# Port.net
KiCad netlist of a schematic drawn in Altium Designer
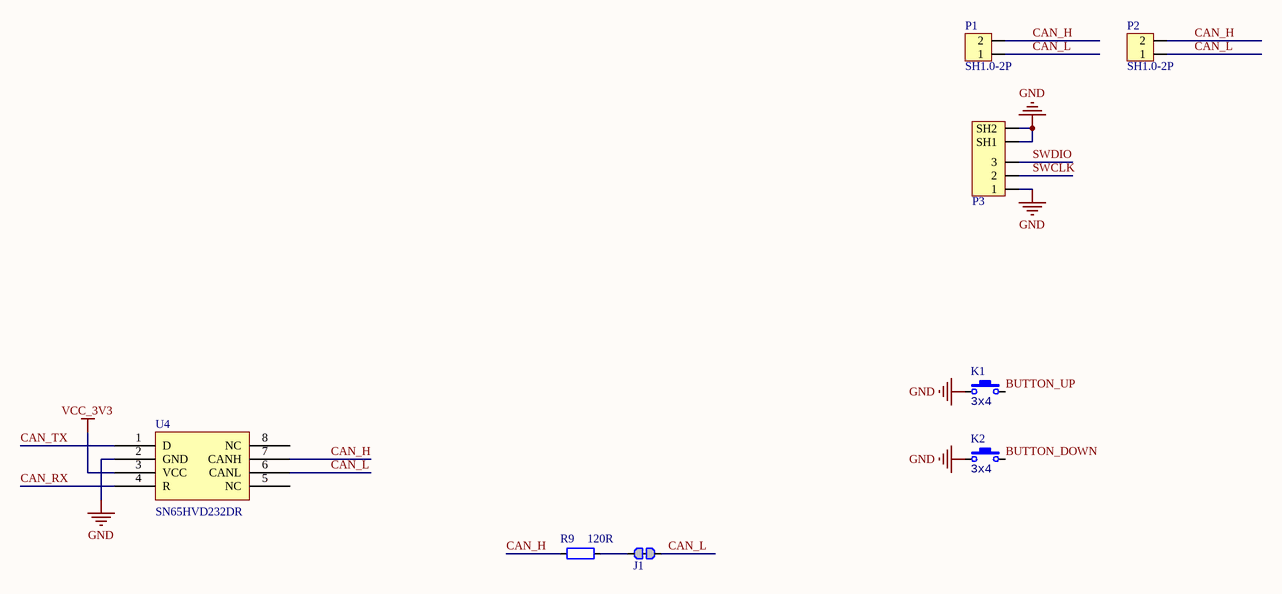
[diagram p0: Port.SchDoc]

(export (version "E")
  (design (tool "Eeschema 10.0.6"))
  (components
    (comp (ref "J1")
      (value "跳线")
      (footprint "0402-0R")
      (description "Resistor")
      (fields (field (name "PUBLISHER") "Altium Limited"))
      (libsource (lib "MyPcbLib") (part "跳线"))
    )
    (comp (ref "K1")
      (value "3x4")
      (footprint "ButtonTACT_3x4x2_180")
      (description "Button")
      (fields (field (name "Comment") "TACT 2P"))
      (libsource (lib "KitSprout") (part "ButtonTACT_3x4x2_180"))
    )
    (comp (ref "K2")
      (value "3x4")
      (footprint "ButtonTACT_3x4x2_180")
      (description "Button")
      (fields (field (name "Comment") "TACT 2P"))
      (libsource (lib "KitSprout") (part "ButtonTACT_3x4x2_180"))
    )
    (comp (ref "P1") (value "SH1.0-2P") (footprint "SH1.0-2P") (libsource (lib "MyPcbLib") (part "SH1.0-2P")))
    (comp (ref "P2") (value "SH1.0-2P") (footprint "SH1.0-2P") (libsource (lib "MyPcbLib") (part "SH1.0-2P")))
    (comp (ref "P3")
      (value "SH1.0-3P")
      (footprint "SH1.0-3P")
      (description "Header")
      (libsource (lib "MyPcbLib") (part "SH1.0-3P"))
    )
    (comp (ref "R9")
      (value "120R")
      (footprint "RES_0402")
      (description "Resistor")
      (libsource (lib "MyPcbLib") (part "电阻-0402"))
    )
    (comp (ref "U4")
      (value "SN65HVD232D")
      (footprint "SO-8")
      (fields
        (field (name "MANUFACTURER") "Texas Instruments")
        (field (name "MANUFACTURER PART NUMBER") "SN65HVD232DR")
      )
      (libsource (lib "MyPcbLib") (part "SN65HVD232D"))
    )
  )
  (nets
    (net (code "1") (name "/BUTTON_DOWN") (class "Default")
      (node (ref "K2") (pin "2") (pinfunction "2_2") (pintype "passive"))
    )
    (net (code "2") (name "/BUTTON_UP") (class "Default")
      (node (ref "K1") (pin "2") (pinfunction "2_2") (pintype "passive"))
    )
    (net (code "3") (name "/CAN_H") (class "Default")
      (node (ref "P1") (pin "2") (pinfunction "2_2") (pintype "passive"))
      (node (ref "P2") (pin "2") (pinfunction "2_2") (pintype "passive"))
      (node (ref "R9") (pin "1") (pinfunction "1_1") (pintype "passive"))
      (node (ref "U4") (pin "7") (pinfunction "CANH_7") (pintype "passive"))
    )
    (net (code "4") (name "/CAN_L") (class "Default")
      (node (ref "J1") (pin "2") (pinfunction "2_2") (pintype "passive"))
      (node (ref "P1") (pin "1") (pinfunction "1_1") (pintype "passive"))
      (node (ref "P2") (pin "1") (pinfunction "1_1") (pintype "passive"))
      (node (ref "U4") (pin "6") (pinfunction "CANL_6") (pintype "passive"))
    )
    (net (code "5") (name "/CAN_RX") (class "Default")
      (node (ref "U4") (pin "4") (pinfunction "R_4") (pintype "passive"))
    )
    (net (code "6") (name "/CAN_TX") (class "Default")
      (node (ref "U4") (pin "1") (pinfunction "D_1") (pintype "passive"))
    )
    (net (code "7") (name "/SWCLK") (class "Default")
      (node (ref "P3") (pin "2") (pinfunction "2_2") (pintype "passive"))
    )
    (net (code "8") (name "/SWDIO") (class "Default")
      (node (ref "P3") (pin "3") (pinfunction "3_3") (pintype "passive"))
    )
    (net (code "9") (name "GND") (class "Default")
      (node (ref "K1") (pin "1") (pinfunction "1_1") (pintype "passive"))
      (node (ref "K2") (pin "1") (pinfunction "1_1") (pintype "passive"))
      (node (ref "P3") (pin "1") (pinfunction "1_1") (pintype "passive"))
      (node (ref "P3") (pin "SH1") (pinfunction "SH1_SH1") (pintype "passive"))
      (node (ref "P3") (pin "SH2") (pinfunction "SH2_SH2") (pintype "passive"))
      (node (ref "U4") (pin "2") (pinfunction "GND_2") (pintype "passive"))
    )
    (net (code "10") (name "Net-(J1-Pad1)") (class "Default")
      (node (ref "J1") (pin "1") (pinfunction "1_1") (pintype "passive"))
      (node (ref "R9") (pin "2") (pinfunction "2_2") (pintype "passive"))
    )
    (net (code "11") (name "VCC_3V3") (class "Default")
      (node (ref "U4") (pin "3") (pinfunction "VCC_3") (pintype "passive"))
    )
    (net (code "12") (name "unconnected-(U4-NC-Pad5)") (class "Default")
      (node (ref "U4") (pin "5") (pinfunction "NC_5") (pintype "passive"))
    )
    (net (code "13") (name "unconnected-(U4-NC-Pad8)") (class "Default")
      (node (ref "U4") (pin "8") (pinfunction "NC_8") (pintype "passive"))
    )
  )
)
